# mayfly_platform_revb.net
KiCad netlist of a schematic drawn in EAGLE
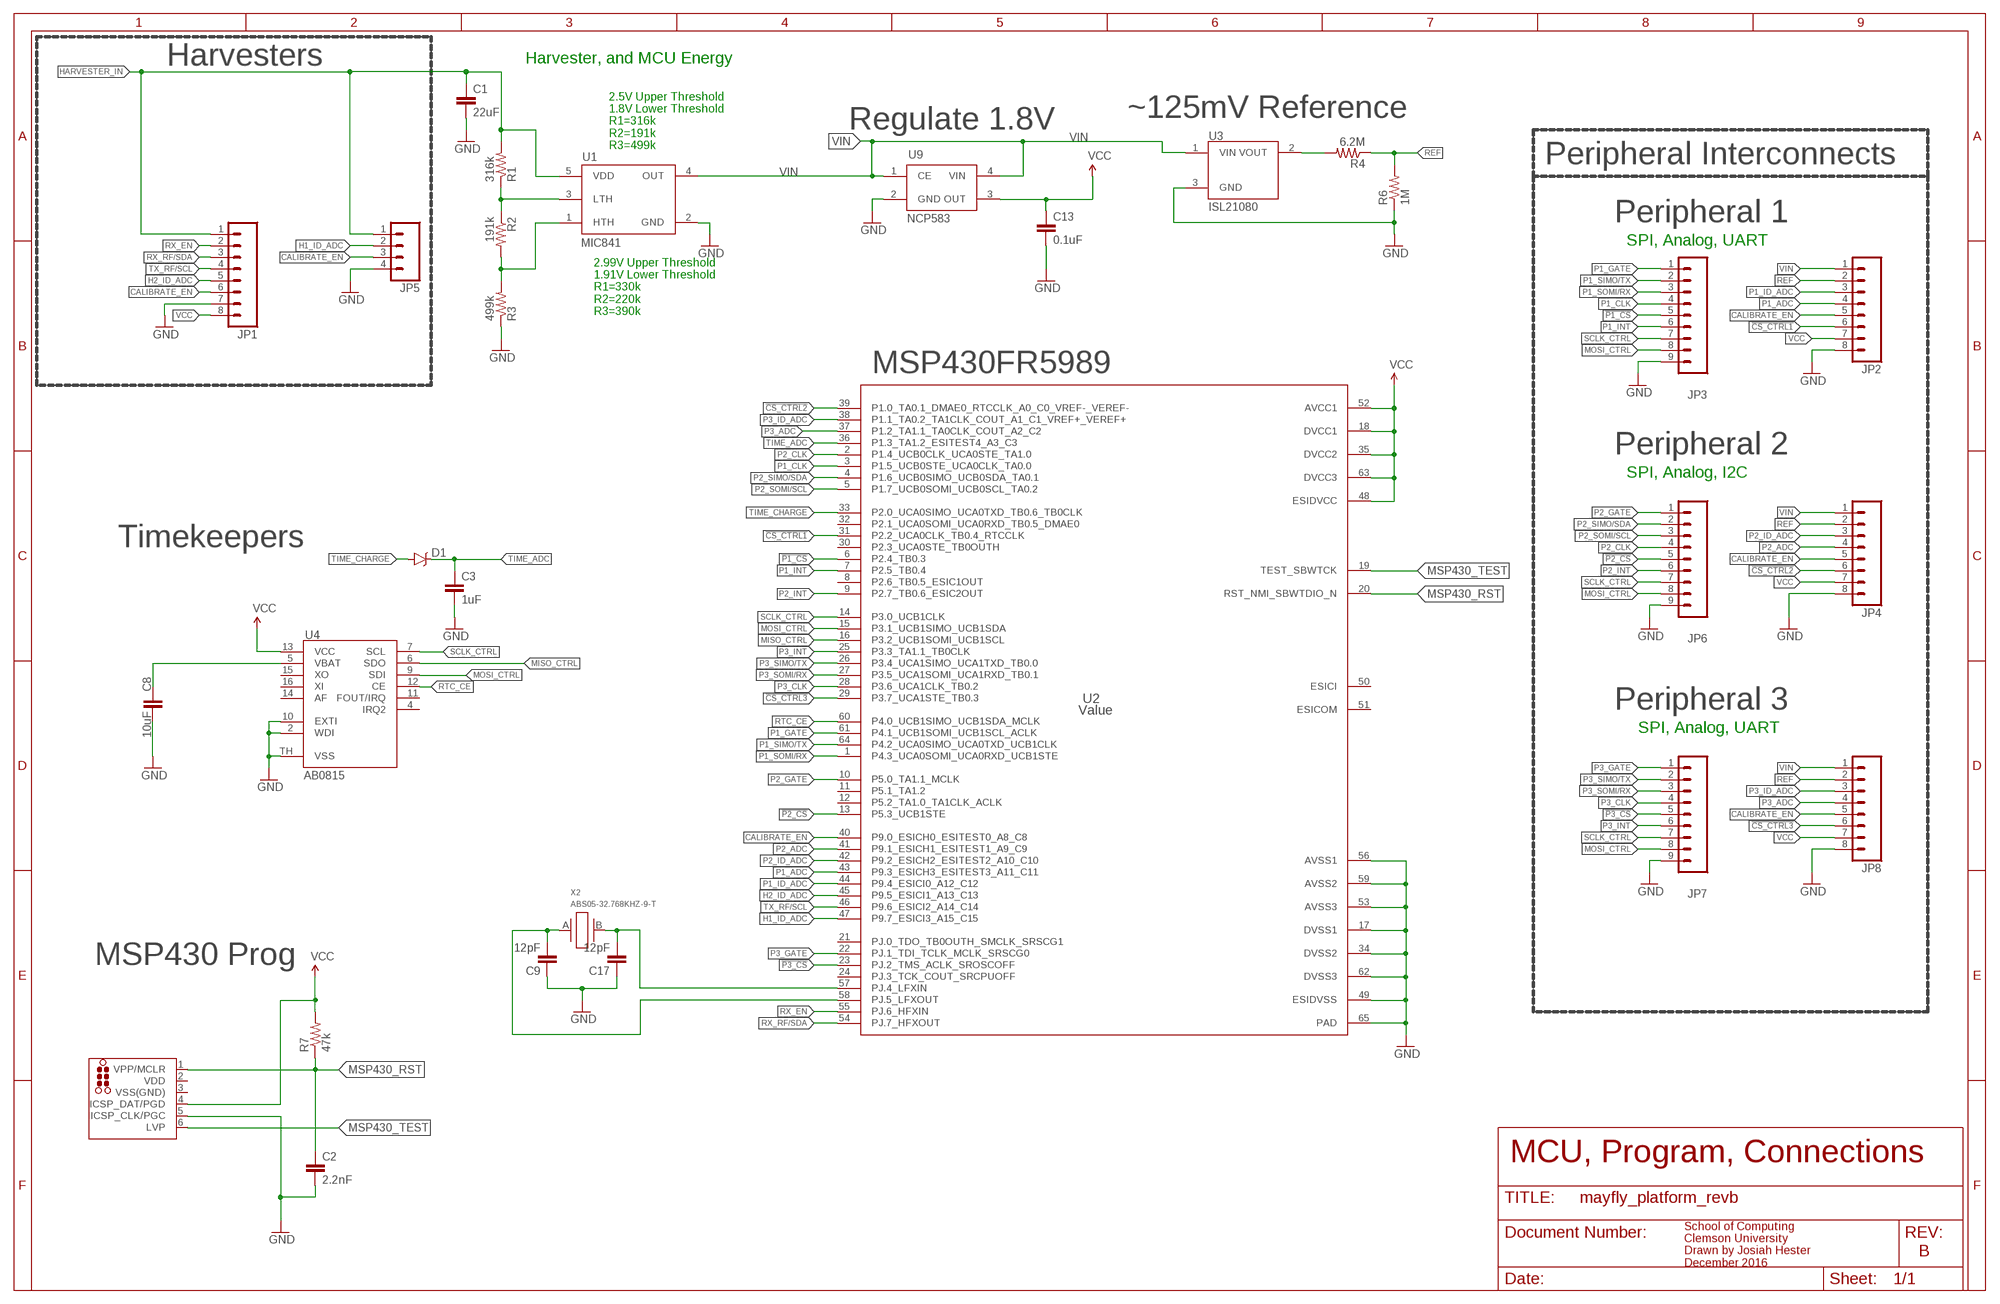
[diagram p0: schematic, sheet 1]

(export (version "E")
  (design (tool "Eeschema 10.0.6"))
  (components
    (comp (ref "C1")
      (value "22uF")
      (footprint "eagle-import:1210")
      (fields (field (name "MANUFACTURERPARTNUMBER") "  CL32A226KAJNNNE"))
      (libsource (lib "eagle-import") (part "CAP1210"))
    )
    (comp (ref "C2")
      (value "2.2nF")
      (footprint "eagle-import:0603")
      (fields (field (name "MPN") "  06035C222KAT2A"))
      (libsource (lib "eagle-import") (part "C-EU0603"))
    )
    (comp (ref "C3")
      (value "1uF")
      (footprint "eagle-import:0603")
      (fields (field (name "MANUFACTURERPARTNUMBER") "  0603YD105KAT2A"))
      (libsource (lib "eagle-import") (part "C-EU0603"))
    )
    (comp (ref "C8")
      (value "10uF")
      (footprint "eagle-import:0805")
      (fields (field (name "MPN") "0805YD106KAT2A"))
      (libsource (lib "eagle-import") (part "CAP0805"))
    )
    (comp (ref "C9")
      (value "12pF")
      (footprint "eagle-import:0603")
      (fields (field (name "MPN") "CL10C120JB8NNNC"))
      (libsource (lib "eagle-import") (part "C-EU0603"))
    )
    (comp (ref "C13")
      (value "0.1uF")
      (footprint "eagle-import:0603")
      (fields (field (name "MANUFACTURERPARTNUMBER") "  0603YC104KAT2A"))
      (libsource (lib "eagle-import") (part "C-EU0603"))
    )
    (comp (ref "C17")
      (value "12pF")
      (footprint "eagle-import:0603")
      (fields (field (name "MPN") "CL10C120JB8NNNC"))
      (libsource (lib "eagle-import") (part "C-EU0603"))
    )
    (comp (ref "D1")
      (value "RB751")
      (footprint "eagle-import:SOD-523")
      (fields (field (name "MPN") "BAS40-02V-V-G-08 "))
      (libsource (lib "eagle-import") (part "DIODE-SCHOTTKY-RB751"))
    )
    (comp (ref "J1")
      (value "TC2030-MCP-NL")
      (footprint "eagle-import:TC2030-MCP-NL")
      (libsource (lib "eagle-import") (part "TC2030-MCP-NL"))
    )
    (comp (ref "JP1")
      (value "M081.27MM")
      (footprint "eagle-import:1X08-1.27MM")
      (fields (field (name "MANUFACTURERPARTNUMBER") "851-43-008-10-001000 "))
      (libsource (lib "eagle-import") (part "M081.27MM"))
    )
    (comp (ref "JP2")
      (value "M081.27MM")
      (footprint "eagle-import:1X08-1.27MM")
      (fields (field (name "MPN") "851-43-008-10-001000 "))
      (libsource (lib "eagle-import") (part "M081.27MM"))
    )
    (comp (ref "JP3")
      (value "M091.27MM")
      (footprint "eagle-import:1X09-1.27MM")
      (fields (field (name "MPN") "851-87-009-10-001101 "))
      (libsource (lib "eagle-import") (part "M091.27MM"))
    )
    (comp (ref "JP4")
      (value "M081.27MM")
      (footprint "eagle-import:1X08-1.27MM")
      (fields (field (name "MPN") "851-43-008-10-001000 "))
      (libsource (lib "eagle-import") (part "M081.27MM"))
    )
    (comp (ref "JP5")
      (value "M041.27MM")
      (footprint "eagle-import:1X04-1.27MM")
      (fields (field (name "MANUFACTURERPARTNUMBER") "851-43-004-10-001000 "))
      (libsource (lib "eagle-import") (part "M041.27MM"))
    )
    (comp (ref "JP6")
      (value "M091.27MM")
      (footprint "eagle-import:1X09-1.27MM")
      (fields (field (name "MPN") "851-87-009-10-001101 "))
      (libsource (lib "eagle-import") (part "M091.27MM"))
    )
    (comp (ref "JP7")
      (value "M091.27MM")
      (footprint "eagle-import:1X09-1.27MM")
      (fields (field (name "MPN") "851-87-009-10-001101 "))
      (libsource (lib "eagle-import") (part "M091.27MM"))
    )
    (comp (ref "JP8")
      (value "M081.27MM")
      (footprint "eagle-import:1X08-1.27MM")
      (fields (field (name "MPN") "851-43-008-10-001000 "))
      (libsource (lib "eagle-import") (part "M081.27MM"))
    )
    (comp (ref "R1")
      (value "316k")
      (footprint "eagle-import:0603")
      (fields (field (name "MANUFACTURERPARTNUMBER") "RC0603FR-07316KL "))
      (libsource (lib "eagle-import") (part "R-EU0603"))
    )
    (comp (ref "R2")
      (value "191k")
      (footprint "eagle-import:0603")
      (fields (field (name "MANUFACTURERPARTNUMBER") "RC0603FR-07191KL "))
      (libsource (lib "eagle-import") (part "R-EU0603"))
    )
    (comp (ref "R3")
      (value "499k")
      (footprint "eagle-import:0603")
      (fields (field (name "MANUFACTURERPARTNUMBER") "RC0603FR-07499KL"))
      (libsource (lib "eagle-import") (part "R-EU0603"))
    )
    (comp (ref "R4")
      (value "6.2M")
      (footprint "eagle-import:0603")
      (fields (field (name "MPN") "CRCW06036M20FKEA"))
      (libsource (lib "eagle-import") (part "R-EU0603"))
    )
    (comp (ref "R6")
      (value "1M")
      (footprint "eagle-import:0603")
      (fields (field (name "MPN") "RC0603FR-071ML"))
      (libsource (lib "eagle-import") (part "R-EU0603"))
    )
    (comp (ref "R7")
      (value "47k")
      (footprint "eagle-import:0603")
      (fields (field (name "MPN") "  CRCW060347K0JNEA"))
      (libsource (lib "eagle-import") (part "R-EU0603"))
    )
    (comp (ref "U1")
      (value "MIC841")
      (footprint "eagle-import:SC70-5")
      (fields (field (name "MPN") "MIC841HYC5-TR"))
      (libsource (lib "eagle-import") (part "MIC841"))
    )
    (comp (ref "U2")
      (value "Value")
      (footprint "eagle-import:RGC0064B")
      (fields
        (field (name "ALTERNATEPARTNUMBER") "MSP430FR5989IRGCT")
        (field (name "MANUFACTURER") "Texas Instruments")
        (field (name "PARTNUMBER") "MSP430FR5989IRGCR")
      )
      (libsource (lib "eagle-import") (part "MSP430FR5989IRGCR"))
    )
    (comp (ref "U3")
      (value "ISL21080")
      (footprint "eagle-import:SOT-23")
      (fields (field (name "MPN") "ISL21080DIH309Z-TK"))
      (libsource (lib "eagle-import") (part "ISL21080"))
    )
    (comp (ref "U4")
      (value "AB0815")
      (footprint "eagle-import:QFN16")
      (fields (field (name "MPN") "AB0815-T3"))
      (libsource (lib "eagle-import") (part "AB0815"))
    )
    (comp (ref "U9")
      (value "NCP583")
      (footprint "eagle-import:SC82-AB_1PRIMARY")
      (fields (field (name "MPN") "NCP583SQ18T1G"))
      (libsource (lib "eagle-import") (part "NCP583"))
    )
    (comp (ref "X2")
      (value "ABS05-32.768KHZ-9-T")
      (footprint "eagle-import:ABS05")
      (fields (field (name "MPN") "ABS05-32.768KHZ-9-T "))
      (libsource (lib "eagle-import") (part "ABS05-32.768KHZ-9-T"))
    )
  )
  (nets
    (net (code "1") (name "/VDD") (class "Default")
      (node (ref "J1") (pin "2") (pinfunction "VDD_2") (pintype "power_in"))
    )
    (net (code "2") (name "/VSS(GND)") (class "Default")
      (node (ref "J1") (pin "3") (pinfunction "VSS(GND)_3") (pintype "power_in"))
    )
    (net (code "3") (name "/~{CS_CTRL1}") (class "Default")
      (node (ref "JP2") (pin "6") (pinfunction "6_6") (pintype "passive"))
      (node (ref "U2") (pin "31") (pinfunction "P2.2_UCA0CLK_TB0.4_RTCCLK_31") (pintype "bidirectional"))
    )
    (net (code "4") (name "/~{CS_CTRL2}") (class "Default")
      (node (ref "JP4") (pin "6") (pinfunction "6_6") (pintype "passive"))
      (node (ref "U2") (pin "39") (pinfunction "P1.0_TA0.1_DMAE0_RTCCLK_A0_C0_VREF-_VEREF-_39") (pintype "bidirectional"))
    )
    (net (code "5") (name "/~{CS_CTRL3}") (class "Default")
      (node (ref "JP8") (pin "6") (pinfunction "6_6") (pintype "passive"))
      (node (ref "U2") (pin "29") (pinfunction "P3.7_UCA1STE_TB0.3_29") (pintype "bidirectional"))
    )
    (net (code "6") (name "/~{P1_CS}") (class "Default")
      (node (ref "JP3") (pin "5") (pinfunction "5_5") (pintype "passive"))
      (node (ref "U2") (pin "6") (pinfunction "P2.4_TB0.3_6") (pintype "bidirectional"))
    )
    (net (code "7") (name "/~{P2_CS}") (class "Default")
      (node (ref "JP6") (pin "5") (pinfunction "5_5") (pintype "passive"))
      (node (ref "U2") (pin "13") (pinfunction "P5.3_UCB1STE_13") (pintype "bidirectional"))
    )
    (net (code "8") (name "/~{P3_CS}") (class "Default")
      (node (ref "JP7") (pin "5") (pinfunction "5_5") (pintype "passive"))
      (node (ref "U2") (pin "23") (pinfunction "PJ.2_TMS_ACLK_SROSCOFF_23") (pintype "bidirectional"))
    )
    (net (code "9") (name "CALIBRATE_EN") (class "Default")
      (node (ref "JP1") (pin "6") (pinfunction "6_6") (pintype "passive"))
      (node (ref "JP2") (pin "5") (pinfunction "5_5") (pintype "passive"))
      (node (ref "JP4") (pin "5") (pinfunction "5_5") (pintype "passive"))
      (node (ref "JP5") (pin "3") (pinfunction "3_3") (pintype "passive"))
      (node (ref "JP8") (pin "5") (pinfunction "5_5") (pintype "passive"))
      (node (ref "U2") (pin "40") (pinfunction "P9.0_ESICH0_ESITEST0_A8_C8_40") (pintype "bidirectional"))
    )
    (net (code "10") (name "GND") (class "Default")
      (node (ref "C1") (pin "2") (pinfunction "2_2") (pintype "passive"))
      (node (ref "C13") (pin "2") (pinfunction "2_2") (pintype "passive"))
      (node (ref "C17") (pin "1") (pinfunction "1_1") (pintype "passive"))
      (node (ref "C2") (pin "2") (pinfunction "2_2") (pintype "passive"))
      (node (ref "C3") (pin "2") (pinfunction "2_2") (pintype "passive"))
      (node (ref "C8") (pin "2") (pinfunction "2_2") (pintype "passive"))
      (node (ref "C9") (pin "1") (pinfunction "1_1") (pintype "passive"))
      (node (ref "J1") (pin "5") (pinfunction "ICSP_CLK/PGC_5") (pintype "output"))
      (node (ref "JP1") (pin "7") (pinfunction "7_7") (pintype "passive"))
      (node (ref "JP2") (pin "8") (pinfunction "8_8") (pintype "passive"))
      (node (ref "JP3") (pin "9") (pinfunction "9_9") (pintype "passive"))
      (node (ref "JP4") (pin "8") (pinfunction "8_8") (pintype "passive"))
      (node (ref "JP5") (pin "4") (pinfunction "4_4") (pintype "passive"))
      (node (ref "JP6") (pin "9") (pinfunction "9_9") (pintype "passive"))
      (node (ref "JP7") (pin "9") (pinfunction "9_9") (pintype "passive"))
      (node (ref "JP8") (pin "8") (pinfunction "8_8") (pintype "passive"))
      (node (ref "R3") (pin "1") (pinfunction "1_1") (pintype "passive"))
      (node (ref "R6") (pin "1") (pinfunction "1_1") (pintype "passive"))
      (node (ref "U1") (pin "2") (pinfunction "GND_2") (pintype "bidirectional"))
      (node (ref "U2") (pin "17") (pinfunction "DVSS1_17") (pintype "power_in"))
      (node (ref "U2") (pin "34") (pinfunction "DVSS2_34") (pintype "power_in"))
      (node (ref "U2") (pin "49") (pinfunction "ESIDVSS_49") (pintype "power_in"))
      (node (ref "U2") (pin "53") (pinfunction "AVSS3_53") (pintype "power_in"))
      (node (ref "U2") (pin "56") (pinfunction "AVSS1_56") (pintype "power_in"))
      (node (ref "U2") (pin "59") (pinfunction "AVSS2_59") (pintype "power_in"))
      (node (ref "U2") (pin "62") (pinfunction "DVSS3_62") (pintype "power_in"))
      (node (ref "U2") (pin "65") (pinfunction "PAD_65") (pintype "power_in"))
      (node (ref "U3") (pin "3") (pinfunction "GND_3") (pintype "bidirectional"))
      (node (ref "U4") (pin "10") (pinfunction "EXTI_10") (pintype "bidirectional"))
      (node (ref "U4") (pin "2") (pinfunction "WDI_2") (pintype "bidirectional"))
      (node (ref "U4") (pin "TH") (pinfunction "VSS_TH") (pintype "bidirectional"))
      (node (ref "U9") (pin "2") (pinfunction "GND_2") (pintype "bidirectional"))
    )
    (net (code "11") (name "H1_ID_ADC") (class "Default")
      (node (ref "JP5") (pin "2") (pinfunction "2_2") (pintype "passive"))
      (node (ref "U2") (pin "47") (pinfunction "P9.7_ESICI3_A15_C15_47") (pintype "bidirectional"))
    )
    (net (code "12") (name "H2_ID_ADC") (class "Default")
      (node (ref "JP1") (pin "5") (pinfunction "5_5") (pintype "passive"))
      (node (ref "U2") (pin "45") (pinfunction "P9.5_ESICI1_A13_C13_45") (pintype "bidirectional"))
    )
    (net (code "13") (name "HARVESTER_IN") (class "Default")
      (node (ref "C1") (pin "1") (pinfunction "1_1") (pintype "passive"))
      (node (ref "JP1") (pin "1") (pinfunction "1_1") (pintype "passive"))
      (node (ref "JP5") (pin "1") (pinfunction "1_1") (pintype "passive"))
      (node (ref "R1") (pin "2") (pinfunction "2_2") (pintype "passive"))
      (node (ref "U1") (pin "5") (pinfunction "VDD_5") (pintype "bidirectional"))
    )
    (net (code "14") (name "MISO_CTRL") (class "Default")
      (node (ref "U2") (pin "16") (pinfunction "P3.2_UCB1SOMI_UCB1SCL_16") (pintype "bidirectional"))
      (node (ref "U4") (pin "6") (pinfunction "SDO_6") (pintype "bidirectional"))
    )
    (net (code "15") (name "MOSI_CTRL") (class "Default")
      (node (ref "JP3") (pin "8") (pinfunction "8_8") (pintype "passive"))
      (node (ref "JP6") (pin "8") (pinfunction "8_8") (pintype "passive"))
      (node (ref "JP7") (pin "8") (pinfunction "8_8") (pintype "passive"))
      (node (ref "U2") (pin "15") (pinfunction "P3.1_UCB1SIMO_UCB1SDA_15") (pintype "bidirectional"))
      (node (ref "U4") (pin "9") (pinfunction "SDI_9") (pintype "bidirectional"))
    )
    (net (code "16") (name "MSP430_RST") (class "Default")
      (node (ref "C2") (pin "1") (pinfunction "1_1") (pintype "passive"))
      (node (ref "J1") (pin "1") (pinfunction "VPP/MCLR_1") (pintype "passive"))
      (node (ref "R7") (pin "1") (pinfunction "1_1") (pintype "passive"))
      (node (ref "U2") (pin "20") (pinfunction "RST_NMI_SBWTDIO_N_20") (pintype "bidirectional"))
    )
    (net (code "17") (name "MSP430_TEST") (class "Default")
      (node (ref "J1") (pin "6") (pinfunction "LVP_6") (pintype "bidirectional"))
      (node (ref "U2") (pin "19") (pinfunction "TEST_SBWTCK_19") (pintype "input"))
    )
    (net (code "18") (name "Net-(U1-HTH)") (class "Default")
      (node (ref "R2") (pin "2") (pinfunction "2_2") (pintype "passive"))
      (node (ref "R3") (pin "2") (pinfunction "2_2") (pintype "passive"))
      (node (ref "U1") (pin "1") (pinfunction "HTH_1") (pintype "bidirectional"))
    )
    (net (code "19") (name "Net-(U1-LTH)") (class "Default")
      (node (ref "R1") (pin "1") (pinfunction "1_1") (pintype "passive"))
      (node (ref "R2") (pin "1") (pinfunction "1_1") (pintype "passive"))
      (node (ref "U1") (pin "3") (pinfunction "LTH_3") (pintype "bidirectional"))
    )
    (net (code "20") (name "Net-(U2-PJ.4_LFXIN)") (class "Default")
      (node (ref "C17") (pin "2") (pinfunction "2_2") (pintype "passive"))
      (node (ref "U2") (pin "57") (pinfunction "PJ.4_LFXIN_57") (pintype "bidirectional"))
      (node (ref "X2") (pin "B") (pinfunction "2_B") (pintype "bidirectional"))
    )
    (net (code "21") (name "Net-(U2-PJ.5_LFXOUT)") (class "Default")
      (node (ref "C9") (pin "2") (pinfunction "2_2") (pintype "passive"))
      (node (ref "U2") (pin "58") (pinfunction "PJ.5_LFXOUT_58") (pintype "bidirectional"))
      (node (ref "X2") (pin "A") (pinfunction "1_A") (pintype "bidirectional"))
    )
    (net (code "22") (name "Net-(U3-VOUT)") (class "Default")
      (node (ref "R4") (pin "2") (pinfunction "2_2") (pintype "passive"))
      (node (ref "U3") (pin "2") (pinfunction "VOUT_2") (pintype "bidirectional"))
    )
    (net (code "23") (name "Net-(U4-VBAT)") (class "Default")
      (node (ref "C8") (pin "1") (pinfunction "1_1") (pintype "passive"))
      (node (ref "U4") (pin "5") (pinfunction "VBAT_5") (pintype "bidirectional"))
    )
    (net (code "24") (name "P1_ADC") (class "Default")
      (node (ref "JP2") (pin "4") (pinfunction "4_4") (pintype "passive"))
      (node (ref "U2") (pin "43") (pinfunction "P9.3_ESICH3_ESITEST3_A11_C11_43") (pintype "bidirectional"))
    )
    (net (code "25") (name "P1_CLK") (class "Default")
      (node (ref "JP3") (pin "4") (pinfunction "4_4") (pintype "passive"))
      (node (ref "U2") (pin "3") (pinfunction "P1.5_UCB0STE_UCA0CLK_TA0.0_3") (pintype "bidirectional"))
    )
    (net (code "26") (name "P1_GATE") (class "Default")
      (node (ref "JP3") (pin "1") (pinfunction "1_1") (pintype "passive"))
      (node (ref "U2") (pin "61") (pinfunction "P4.1_UCB1SOMI_UCB1SCL_ACLK_61") (pintype "bidirectional"))
    )
    (net (code "27") (name "P1_ID_ADC") (class "Default")
      (node (ref "JP2") (pin "3") (pinfunction "3_3") (pintype "passive"))
      (node (ref "U2") (pin "44") (pinfunction "P9.4_ESICI0_A12_C12_44") (pintype "bidirectional"))
    )
    (net (code "28") (name "P1_INT") (class "Default")
      (node (ref "JP3") (pin "6") (pinfunction "6_6") (pintype "passive"))
      (node (ref "U2") (pin "7") (pinfunction "P2.5_TB0.4_7") (pintype "bidirectional"))
    )
    (net (code "29") (name "P1_SIMO{slash}TX") (class "Default")
      (node (ref "JP3") (pin "2") (pinfunction "2_2") (pintype "passive"))
      (node (ref "U2") (pin "64") (pinfunction "P4.2_UCA0SIMO_UCA0TXD_UCB1CLK_64") (pintype "bidirectional"))
    )
    (net (code "30") (name "P1_SOMI{slash}RX") (class "Default")
      (node (ref "JP3") (pin "3") (pinfunction "3_3") (pintype "passive"))
      (node (ref "U2") (pin "1") (pinfunction "P4.3_UCA0SOMI_UCA0RXD_UCB1STE_1") (pintype "bidirectional"))
    )
    (net (code "31") (name "P2_ADC") (class "Default")
      (node (ref "JP4") (pin "4") (pinfunction "4_4") (pintype "passive"))
      (node (ref "U2") (pin "41") (pinfunction "P9.1_ESICH1_ESITEST1_A9_C9_41") (pintype "bidirectional"))
    )
    (net (code "32") (name "P2_CLK") (class "Default")
      (node (ref "JP6") (pin "4") (pinfunction "4_4") (pintype "passive"))
      (node (ref "U2") (pin "2") (pinfunction "P1.4_UCB0CLK_UCA0STE_TA1.0_2") (pintype "bidirectional"))
    )
    (net (code "33") (name "P2_GATE") (class "Default")
      (node (ref "JP6") (pin "1") (pinfunction "1_1") (pintype "passive"))
      (node (ref "U2") (pin "10") (pinfunction "P5.0_TA1.1_MCLK_10") (pintype "bidirectional"))
    )
    (net (code "34") (name "P2_ID_ADC") (class "Default")
      (node (ref "JP4") (pin "3") (pinfunction "3_3") (pintype "passive"))
      (node (ref "U2") (pin "42") (pinfunction "P9.2_ESICH2_ESITEST2_A10_C10_42") (pintype "bidirectional"))
    )
    (net (code "35") (name "P2_INT") (class "Default")
      (node (ref "JP6") (pin "6") (pinfunction "6_6") (pintype "passive"))
      (node (ref "U2") (pin "9") (pinfunction "P2.7_TB0.6_ESIC2OUT_9") (pintype "bidirectional"))
    )
    (net (code "36") (name "P2_SIMO{slash}SDA") (class "Default")
      (node (ref "JP6") (pin "2") (pinfunction "2_2") (pintype "passive"))
      (node (ref "U2") (pin "4") (pinfunction "P1.6_UCB0SIMO_UCB0SDA_TA0.1_4") (pintype "bidirectional"))
    )
    (net (code "37") (name "P2_SOMI{slash}SCL") (class "Default")
      (node (ref "JP6") (pin "3") (pinfunction "3_3") (pintype "passive"))
      (node (ref "U2") (pin "5") (pinfunction "P1.7_UCB0SOMI_UCB0SCL_TA0.2_5") (pintype "bidirectional"))
    )
    (net (code "38") (name "P3_ADC") (class "Default")
      (node (ref "JP8") (pin "4") (pinfunction "4_4") (pintype "passive"))
      (node (ref "U2") (pin "37") (pinfunction "P1.2_TA1.1_TA0CLK_COUT_A2_C2_37") (pintype "bidirectional"))
    )
    (net (code "39") (name "P3_CLK") (class "Default")
      (node (ref "JP7") (pin "4") (pinfunction "4_4") (pintype "passive"))
      (node (ref "U2") (pin "28") (pinfunction "P3.6_UCA1CLK_TB0.2_28") (pintype "bidirectional"))
    )
    (net (code "40") (name "P3_GATE") (class "Default")
      (node (ref "JP7") (pin "1") (pinfunction "1_1") (pintype "passive"))
      (node (ref "U2") (pin "22") (pinfunction "PJ.1_TDI_TCLK_MCLK_SRSCG0_22") (pintype "bidirectional"))
    )
    (net (code "41") (name "P3_ID_ADC") (class "Default")
      (node (ref "JP8") (pin "3") (pinfunction "3_3") (pintype "passive"))
      (node (ref "U2") (pin "38") (pinfunction "P1.1_TA0.2_TA1CLK_COUT_A1_C1_VREF+_VEREF+_38") (pintype "bidirectional"))
    )
    (net (code "42") (name "P3_INT") (class "Default")
      (node (ref "JP7") (pin "6") (pinfunction "6_6") (pintype "passive"))
      (node (ref "U2") (pin "25") (pinfunction "P3.3_TA1.1_TB0CLK_25") (pintype "bidirectional"))
    )
    (net (code "43") (name "P3_SIMO{slash}TX") (class "Default")
      (node (ref "JP7") (pin "2") (pinfunction "2_2") (pintype "passive"))
      (node (ref "U2") (pin "26") (pinfunction "P3.4_UCA1SIMO_UCA1TXD_TB0.0_26") (pintype "bidirectional"))
    )
    (net (code "44") (name "P3_SOMI{slash}RX") (class "Default")
      (node (ref "JP7") (pin "3") (pinfunction "3_3") (pintype "passive"))
      (node (ref "U2") (pin "27") (pinfunction "P3.5_UCA1SOMI_UCA1RXD_TB0.1_27") (pintype "bidirectional"))
    )
    (net (code "45") (name "REF") (class "Default")
      (node (ref "JP2") (pin "2") (pinfunction "2_2") (pintype "passive"))
      (node (ref "JP4") (pin "2") (pinfunction "2_2") (pintype "passive"))
      (node (ref "JP8") (pin "2") (pinfunction "2_2") (pintype "passive"))
      (node (ref "R4") (pin "1") (pinfunction "1_1") (pintype "passive"))
      (node (ref "R6") (pin "2") (pinfunction "2_2") (pintype "passive"))
    )
    (net (code "46") (name "RTC_CE") (class "Default")
      (node (ref "U2") (pin "60") (pinfunction "P4.0_UCB1SIMO_UCB1SDA_MCLK_60") (pintype "bidirectional"))
      (node (ref "U4") (pin "12") (pinfunction "CE_12") (pintype "bidirectional"))
    )
    (net (code "47") (name "RX_EN") (class "Default")
      (node (ref "JP1") (pin "2") (pinfunction "2_2") (pintype "passive"))
      (node (ref "U2") (pin "55") (pinfunction "PJ.6_HFXIN_55") (pintype "bidirectional"))
    )
    (net (code "48") (name "RX_RF{slash}SDA") (class "Default")
      (node (ref "JP1") (pin "3") (pinfunction "3_3") (pintype "passive"))
      (node (ref "U2") (pin "54") (pinfunction "PJ.7_HFXOUT_54") (pintype "bidirectional"))
    )
    (net (code "49") (name "SCLK_CTRL") (class "Default")
      (node (ref "JP3") (pin "7") (pinfunction "7_7") (pintype "passive"))
      (node (ref "JP6") (pin "7") (pinfunction "7_7") (pintype "passive"))
      (node (ref "JP7") (pin "7") (pinfunction "7_7") (pintype "passive"))
      (node (ref "U2") (pin "14") (pinfunction "P3.0_UCB1CLK_14") (pintype "bidirectional"))
      (node (ref "U4") (pin "7") (pinfunction "SCL_7") (pintype "bidirectional"))
    )
    (net (code "50") (name "TIME_ADC") (class "Default")
      (node (ref "C3") (pin "1") (pinfunction "1_1") (pintype "passive"))
      (node (ref "D1") (pin "C") (pinfunction "C_C") (pintype "passive"))
      (node (ref "U2") (pin "36") (pinfunction "P1.3_TA1.2_ESITEST4_A3_C3_36") (pintype "bidirectional"))
    )
    (net (code "51") (name "TIME_CHARGE") (class "Default")
      (node (ref "D1") (pin "A") (pinfunction "A_A") (pintype "passive"))
      (node (ref "U2") (pin "33") (pinfunction "P2.0_UCA0SIMO_UCA0TXD_TB0.6_TB0CLK_33") (pintype "bidirectional"))
    )
    (net (code "52") (name "TX_RF{slash}SCL") (class "Default")
      (node (ref "JP1") (pin "4") (pinfunction "4_4") (pintype "passive"))
      (node (ref "U2") (pin "46") (pinfunction "P9.6_ESICI2_A14_C14_46") (pintype "bidirectional"))
    )
    (net (code "53") (name "VCC") (class "Default")
      (node (ref "C13") (pin "1") (pinfunction "1_1") (pintype "passive"))
      (node (ref "J1") (pin "4") (pinfunction "ICSP_DAT/PGD_4") (pintype "bidirectional"))
      (node (ref "JP1") (pin "8") (pinfunction "8_8") (pintype "passive"))
      (node (ref "JP2") (pin "7") (pinfunction "7_7") (pintype "passive"))
      (node (ref "JP4") (pin "7") (pinfunction "7_7") (pintype "passive"))
      (node (ref "JP8") (pin "7") (pinfunction "7_7") (pintype "passive"))
      (node (ref "R7") (pin "2") (pinfunction "2_2") (pintype "passive"))
      (node (ref "U2") (pin "18") (pinfunction "DVCC1_18") (pintype "power_in"))
      (node (ref "U2") (pin "35") (pinfunction "DVCC2_35") (pintype "power_in"))
      (node (ref "U2") (pin "48") (pinfunction "ESIDVCC_48") (pintype "power_in"))
      (node (ref "U2") (pin "52") (pinfunction "AVCC1_52") (pintype "power_in"))
      (node (ref "U2") (pin "63") (pinfunction "DVCC3_63") (pintype "power_in"))
      (node (ref "U4") (pin "13") (pinfunction "VCC_13") (pintype "bidirectional"))
      (node (ref "U9") (pin "3") (pinfunction "OUT_3") (pintype "bidirectional"))
    )
    (net (code "54") (name "VIN") (class "Default")
      (node (ref "JP2") (pin "1") (pinfunction "1_1") (pintype "passive"))
      (node (ref "JP4") (pin "1") (pinfunction "1_1") (pintype "passive"))
      (node (ref "JP8") (pin "1") (pinfunction "1_1") (pintype "passive"))
      (node (ref "U1") (pin "4") (pinfunction "OUT_4") (pintype "bidirectional"))
      (node (ref "U3") (pin "1") (pinfunction "VIN_1") (pintype "bidirectional"))
      (node (ref "U9") (pin "1") (pinfunction "CE_1") (pintype "bidirectional"))
      (node (ref "U9") (pin "4") (pinfunction "VIN_4") (pintype "bidirectional"))
    )
    (net (code "55") (name "unconnected-(U2-ESICI-Pad50)") (class "Default")
      (node (ref "U2") (pin "50") (pinfunction "ESICI_50") (pintype "input"))
    )
    (net (code "56") (name "unconnected-(U2-ESICOM-Pad51)") (class "Default")
      (node (ref "U2") (pin "51") (pinfunction "ESICOM_51") (pintype "passive"))
    )
    (net (code "57") (name "unconnected-(U2-P2.1_UCA0SOMI_UCA0RXD_TB0.5_DMAE0-Pad32)") (class "Default")
      (node (ref "U2") (pin "32") (pinfunction "P2.1_UCA0SOMI_UCA0RXD_TB0.5_DMAE0_32") (pintype "bidirectional"))
    )
    (net (code "58") (name "unconnected-(U2-P2.3_UCA0STE_TB0OUTH-Pad30)") (class "Default")
      (node (ref "U2") (pin "30") (pinfunction "P2.3_UCA0STE_TB0OUTH_30") (pintype "bidirectional"))
    )
    (net (code "59") (name "unconnected-(U2-P2.6_TB0.5_ESIC1OUT-Pad8)") (class "Default")
      (node (ref "U2") (pin "8") (pinfunction "P2.6_TB0.5_ESIC1OUT_8") (pintype "bidirectional"))
    )
    (net (code "60") (name "unconnected-(U2-P5.1_TA1.2-Pad11)") (class "Default")
      (node (ref "U2") (pin "11") (pinfunction "P5.1_TA1.2_11") (pintype "bidirectional"))
    )
    (net (code "61") (name "unconnected-(U2-P5.2_TA1.0_TA1CLK_ACLK-Pad12)") (class "Default")
      (node (ref "U2") (pin "12") (pinfunction "P5.2_TA1.0_TA1CLK_ACLK_12") (pintype "bidirectional"))
    )
    (net (code "62") (name "unconnected-(U2-PJ.0_TDO_TB0OUTH_SMCLK_SRSCG1-Pad21)") (class "Default")
      (node (ref "U2") (pin "21") (pinfunction "PJ.0_TDO_TB0OUTH_SMCLK_SRSCG1_21") (pintype "bidirectional"))
    )
    (net (code "63") (name "unconnected-(U2-PJ.3_TCK_COUT_SRCPUOFF-Pad24)") (class "Default")
      (node (ref "U2") (pin "24") (pinfunction "PJ.3_TCK_COUT_SRCPUOFF_24") (pintype "bidirectional"))
    )
    (net (code "64") (name "unconnected-(U4-AF-Pad14)") (class "Default")
      (node (ref "U4") (pin "14") (pinfunction "AF_14") (pintype "bidirectional"))
    )
    (net (code "65") (name "unconnected-(U4-FOUT{slash}IRQ-Pad11)") (class "Default")
      (node (ref "U4") (pin "11") (pinfunction "FOUT/IRQ_11") (pintype "bidirectional"))
    )
    (net (code "66") (name "unconnected-(U4-IRQ2-Pad4)") (class "Default")
      (node (ref "U4") (pin "4") (pinfunction "IRQ2_4") (pintype "bidirectional"))
    )
    (net (code "67") (name "unconnected-(U4-XI-Pad16)") (class "Default")
      (node (ref "U4") (pin "16") (pinfunction "XI_16") (pintype "bidirectional"))
    )
    (net (code "68") (name "unconnected-(U4-XO-Pad15)") (class "Default")
      (node (ref "U4") (pin "15") (pinfunction "XO_15") (pintype "bidirectional"))
    )
  )
)
